# Sensor_Multiplexation.net
KiCad netlist of a schematic drawn in Altium Designer
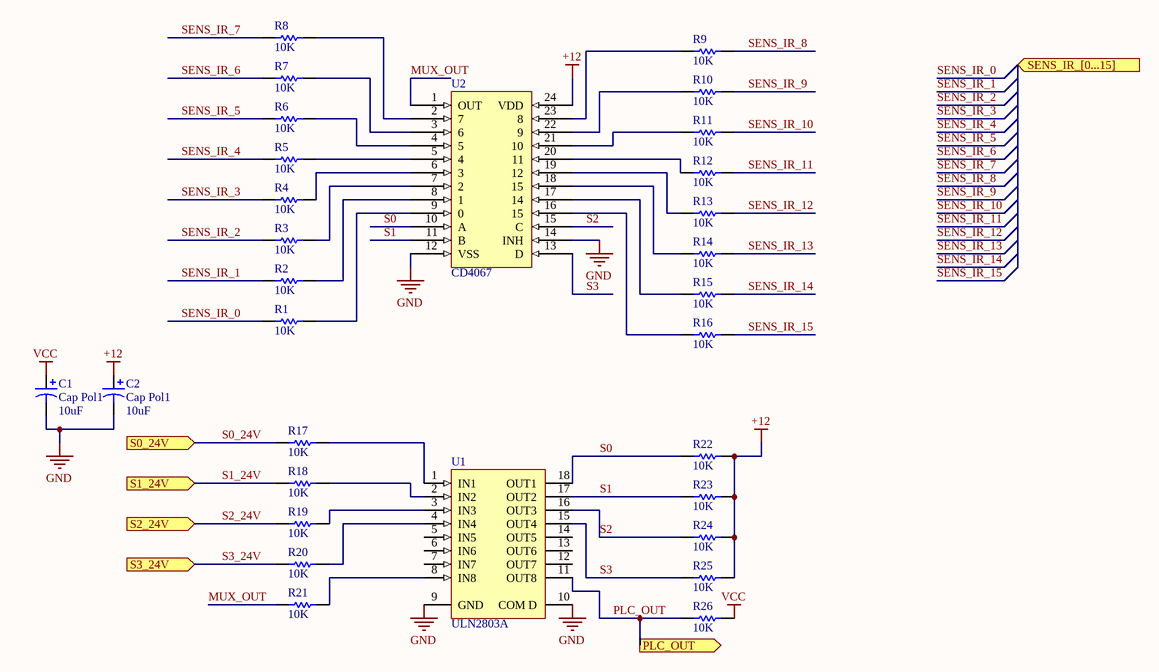
[diagram p0: Sensor_Multiplexation.SchDoc]

(export (version "E")
  (design (tool "Eeschema 10.0.6"))
  (components
    (comp (ref "C1")
      (value "Cap Pol1")
      (footprint "RB7.6-15")
      (description "Polarized Capacitor (Radial)")
      (fields (field (name "ALTIUM_VALUE") "10uF") (field (name "PUBLISHER") "Altium Limited"))
      (libsource (lib "Miscellaneous Devices") (part "Cap Pol1"))
    )
    (comp (ref "C2")
      (value "Cap Pol1")
      (footprint "RB7.6-15")
      (description "Polarized Capacitor (Radial)")
      (fields (field (name "ALTIUM_VALUE") "10uF") (field (name "PUBLISHER") "Altium Limited"))
      (libsource (lib "Miscellaneous Devices") (part "Cap Pol1"))
    )
    (comp (ref "R1")
      (value "10K")
      (footprint "AXIAL-0.3")
      (description "Resistor")
      (fields (field (name "Comment") "Res1") (field (name "PUBLISHER") "Altium Limited"))
      (libsource (lib "Miscellaneous Devices") (part "Res1"))
    )
    (comp (ref "R2")
      (value "10K")
      (footprint "AXIAL-0.3")
      (description "Resistor")
      (fields (field (name "Comment") "Res1") (field (name "PUBLISHER") "Altium Limited"))
      (libsource (lib "Miscellaneous Devices") (part "Res1"))
    )
    (comp (ref "R3")
      (value "10K")
      (footprint "AXIAL-0.3")
      (description "Resistor")
      (fields (field (name "Comment") "Res1") (field (name "PUBLISHER") "Altium Limited"))
      (libsource (lib "Miscellaneous Devices") (part "Res1"))
    )
    (comp (ref "R4")
      (value "10K")
      (footprint "AXIAL-0.3")
      (description "Resistor")
      (fields (field (name "Comment") "Res1") (field (name "PUBLISHER") "Altium Limited"))
      (libsource (lib "Miscellaneous Devices") (part "Res1"))
    )
    (comp (ref "R5")
      (value "10K")
      (footprint "AXIAL-0.3")
      (description "Resistor")
      (fields (field (name "Comment") "Res1") (field (name "PUBLISHER") "Altium Limited"))
      (libsource (lib "Miscellaneous Devices") (part "Res1"))
    )
    (comp (ref "R6")
      (value "10K")
      (footprint "AXIAL-0.3")
      (description "Resistor")
      (fields (field (name "Comment") "Res1") (field (name "PUBLISHER") "Altium Limited"))
      (libsource (lib "Miscellaneous Devices") (part "Res1"))
    )
    (comp (ref "R7")
      (value "10K")
      (footprint "AXIAL-0.3")
      (description "Resistor")
      (fields (field (name "Comment") "Res1") (field (name "PUBLISHER") "Altium Limited"))
      (libsource (lib "Miscellaneous Devices") (part "Res1"))
    )
    (comp (ref "R8")
      (value "10K")
      (footprint "AXIAL-0.3")
      (description "Resistor")
      (fields (field (name "Comment") "Res1") (field (name "PUBLISHER") "Altium Limited"))
      (libsource (lib "Miscellaneous Devices") (part "Res1"))
    )
    (comp (ref "R9")
      (value "10K")
      (footprint "AXIAL-0.3")
      (description "Resistor")
      (fields (field (name "Comment") "Res1") (field (name "PUBLISHER") "Altium Limited"))
      (libsource (lib "Miscellaneous Devices") (part "Res1"))
    )
    (comp (ref "R10")
      (value "10K")
      (footprint "AXIAL-0.3")
      (description "Resistor")
      (fields (field (name "Comment") "Res1") (field (name "PUBLISHER") "Altium Limited"))
      (libsource (lib "Miscellaneous Devices") (part "Res1"))
    )
    (comp (ref "R11")
      (value "10K")
      (footprint "AXIAL-0.3")
      (description "Resistor")
      (fields (field (name "Comment") "Res1") (field (name "PUBLISHER") "Altium Limited"))
      (libsource (lib "Miscellaneous Devices") (part "Res1"))
    )
    (comp (ref "R12")
      (value "10K")
      (footprint "AXIAL-0.3")
      (description "Resistor")
      (fields (field (name "Comment") "Res1") (field (name "PUBLISHER") "Altium Limited"))
      (libsource (lib "Miscellaneous Devices") (part "Res1"))
    )
    (comp (ref "R13")
      (value "10K")
      (footprint "AXIAL-0.3")
      (description "Resistor")
      (fields (field (name "Comment") "Res1") (field (name "PUBLISHER") "Altium Limited"))
      (libsource (lib "Miscellaneous Devices") (part "Res1"))
    )
    (comp (ref "R14")
      (value "10K")
      (footprint "AXIAL-0.3")
      (description "Resistor")
      (fields (field (name "Comment") "Res1") (field (name "PUBLISHER") "Altium Limited"))
      (libsource (lib "Miscellaneous Devices") (part "Res1"))
    )
    (comp (ref "R15")
      (value "10K")
      (footprint "AXIAL-0.3")
      (description "Resistor")
      (fields (field (name "Comment") "Res1") (field (name "PUBLISHER") "Altium Limited"))
      (libsource (lib "Miscellaneous Devices") (part "Res1"))
    )
    (comp (ref "R16")
      (value "10K")
      (footprint "AXIAL-0.3")
      (description "Resistor")
      (fields (field (name "Comment") "Res1") (field (name "PUBLISHER") "Altium Limited"))
      (libsource (lib "Miscellaneous Devices") (part "Res1"))
    )
    (comp (ref "R17")
      (value "10K")
      (footprint "AXIAL-0.3")
      (description "Resistor")
      (fields (field (name "Comment") "Res1") (field (name "PUBLISHER") "Altium Limited"))
      (libsource (lib "Miscellaneous Devices") (part "Res1"))
    )
    (comp (ref "R18")
      (value "10K")
      (footprint "AXIAL-0.3")
      (description "Resistor")
      (fields (field (name "Comment") "Res1") (field (name "PUBLISHER") "Altium Limited"))
      (libsource (lib "Miscellaneous Devices") (part "Res1"))
    )
    (comp (ref "R19")
      (value "10K")
      (footprint "AXIAL-0.3")
      (description "Resistor")
      (fields (field (name "Comment") "Res1") (field (name "PUBLISHER") "Altium Limited"))
      (libsource (lib "Miscellaneous Devices") (part "Res1"))
    )
    (comp (ref "R20")
      (value "10K")
      (footprint "AXIAL-0.3")
      (description "Resistor")
      (fields (field (name "Comment") "Res1") (field (name "PUBLISHER") "Altium Limited"))
      (libsource (lib "Miscellaneous Devices") (part "Res1"))
    )
    (comp (ref "R21")
      (value "10K")
      (footprint "AXIAL-0.3")
      (description "Resistor")
      (fields (field (name "Comment") "Res1") (field (name "PUBLISHER") "Altium Limited"))
      (libsource (lib "Miscellaneous Devices") (part "Res1"))
    )
    (comp (ref "R22")
      (value "10K")
      (footprint "AXIAL-0.3")
      (description "Resistor")
      (fields (field (name "Comment") "Res1") (field (name "PUBLISHER") "Altium Limited"))
      (libsource (lib "Miscellaneous Devices") (part "Res1"))
    )
    (comp (ref "R23")
      (value "10K")
      (footprint "AXIAL-0.3")
      (description "Resistor")
      (fields (field (name "Comment") "Res1") (field (name "PUBLISHER") "Altium Limited"))
      (libsource (lib "Miscellaneous Devices") (part "Res1"))
    )
    (comp (ref "R24")
      (value "10K")
      (footprint "AXIAL-0.3")
      (description "Resistor")
      (fields (field (name "Comment") "Res1") (field (name "PUBLISHER") "Altium Limited"))
      (libsource (lib "Miscellaneous Devices") (part "Res1"))
    )
    (comp (ref "R25")
      (value "10K")
      (footprint "AXIAL-0.3")
      (description "Resistor")
      (fields (field (name "Comment") "Res1") (field (name "PUBLISHER") "Altium Limited"))
      (libsource (lib "Miscellaneous Devices") (part "Res1"))
    )
    (comp (ref "R26")
      (value "10K")
      (footprint "AXIAL-0.3")
      (description "Resistor")
      (fields (field (name "Comment") "Res1") (field (name "PUBLISHER") "Altium Limited"))
      (libsource (lib "Miscellaneous Devices") (part "Res1"))
    )
    (comp (ref "U1")
      (value "ULN2803A")
      (footprint "A18")
      (description "High-Voltage, High-Current Darlington Array")
      (fields (field (name "PUBLISHER") "Altium Limited"))
      (libsource (lib "Allegro Interface Darlington Driver") (part "ULN2803A"))
    )
    (comp (ref "U2") (value "CD4067") (libsource (lib "RobotLib") (part "CD4067")))
  )
  (nets
    (net (code "1") (name "+12") (class "Default")
      (node (ref "C2") (pin "1") (pinfunction "1_1") (pintype "passive"))
      (node (ref "R22") (pin "2") (pinfunction "2_2") (pintype "passive"))
      (node (ref "R23") (pin "2") (pinfunction "2_2") (pintype "passive"))
      (node (ref "R24") (pin "2") (pinfunction "2_2") (pintype "passive"))
      (node (ref "R25") (pin "2") (pinfunction "2_2") (pintype "passive"))
      (node (ref "U2") (pin "24") (pinfunction "VDD_24") (pintype "input"))
    )
    (net (code "2") (name "/MUX_OUT") (class "Default")
      (node (ref "R21") (pin "1") (pinfunction "1_1") (pintype "passive"))
      (node (ref "U2") (pin "1") (pinfunction "OUT_1") (pintype "input"))
    )
    (net (code "3") (name "/PLC_OUT") (class "Default")
      (node (ref "R26") (pin "1") (pinfunction "1_1") (pintype "passive"))
      (node (ref "U1") (pin "11") (pinfunction "OUT8_11") (pintype "open_collector"))
    )
    (net (code "4") (name "/S0") (class "Default")
      (node (ref "R22") (pin "1") (pinfunction "1_1") (pintype "passive"))
      (node (ref "U1") (pin "18") (pinfunction "OUT1_18") (pintype "open_collector"))
      (node (ref "U2") (pin "10") (pinfunction "A_10") (pintype "input"))
    )
    (net (code "5") (name "/S0_24V") (class "Default")
      (node (ref "R17") (pin "1") (pinfunction "1_1") (pintype "passive"))
    )
    (net (code "6") (name "/S1") (class "Default")
      (node (ref "R23") (pin "1") (pinfunction "1_1") (pintype "passive"))
      (node (ref "U1") (pin "17") (pinfunction "OUT2_17") (pintype "open_collector"))
      (node (ref "U2") (pin "11") (pinfunction "B_11") (pintype "input"))
    )
    (net (code "7") (name "/S1_24V") (class "Default")
      (node (ref "R18") (pin "1") (pinfunction "1_1") (pintype "passive"))
    )
    (net (code "8") (name "/S2") (class "Default")
      (node (ref "R24") (pin "1") (pinfunction "1_1") (pintype "passive"))
      (node (ref "U1") (pin "16") (pinfunction "OUT3_16") (pintype "open_collector"))
      (node (ref "U2") (pin "15") (pinfunction "C_15") (pintype "input"))
    )
    (net (code "9") (name "/S2_24V") (class "Default")
      (node (ref "R19") (pin "1") (pinfunction "1_1") (pintype "passive"))
    )
    (net (code "10") (name "/S3") (class "Default")
      (node (ref "R25") (pin "1") (pinfunction "1_1") (pintype "passive"))
      (node (ref "U1") (pin "15") (pinfunction "OUT4_15") (pintype "open_collector"))
      (node (ref "U2") (pin "13") (pinfunction "D_13") (pintype "input"))
    )
    (net (code "11") (name "/S3_24V") (class "Default")
      (node (ref "R20") (pin "1") (pinfunction "1_1") (pintype "passive"))
    )
    (net (code "12") (name "/SENS_IR_0") (class "Default")
      (node (ref "R1") (pin "1") (pinfunction "1_1") (pintype "passive"))
    )
    (net (code "13") (name "/SENS_IR_1") (class "Default")
      (node (ref "R2") (pin "1") (pinfunction "1_1") (pintype "passive"))
    )
    (net (code "14") (name "/SENS_IR_2") (class "Default")
      (node (ref "R3") (pin "1") (pinfunction "1_1") (pintype "passive"))
    )
    (net (code "15") (name "/SENS_IR_3") (class "Default")
      (node (ref "R4") (pin "1") (pinfunction "1_1") (pintype "passive"))
    )
    (net (code "16") (name "/SENS_IR_4") (class "Default")
      (node (ref "R5") (pin "1") (pinfunction "1_1") (pintype "passive"))
    )
    (net (code "17") (name "/SENS_IR_5") (class "Default")
      (node (ref "R6") (pin "1") (pinfunction "1_1") (pintype "passive"))
    )
    (net (code "18") (name "/SENS_IR_6") (class "Default")
      (node (ref "R7") (pin "1") (pinfunction "1_1") (pintype "passive"))
    )
    (net (code "19") (name "/SENS_IR_7") (class "Default")
      (node (ref "R8") (pin "1") (pinfunction "1_1") (pintype "passive"))
    )
    (net (code "20") (name "/SENS_IR_8") (class "Default")
      (node (ref "R9") (pin "2") (pinfunction "2_2") (pintype "passive"))
    )
    (net (code "21") (name "/SENS_IR_9") (class "Default")
      (node (ref "R10") (pin "2") (pinfunction "2_2") (pintype "passive"))
    )
    (net (code "22") (name "/SENS_IR_10") (class "Default")
      (node (ref "R11") (pin "2") (pinfunction "2_2") (pintype "passive"))
    )
    (net (code "23") (name "/SENS_IR_11") (class "Default")
      (node (ref "R12") (pin "2") (pinfunction "2_2") (pintype "passive"))
    )
    (net (code "24") (name "/SENS_IR_12") (class "Default")
      (node (ref "R13") (pin "2") (pinfunction "2_2") (pintype "passive"))
    )
    (net (code "25") (name "/SENS_IR_13") (class "Default")
      (node (ref "R14") (pin "2") (pinfunction "2_2") (pintype "passive"))
    )
    (net (code "26") (name "/SENS_IR_14") (class "Default")
      (node (ref "R15") (pin "2") (pinfunction "2_2") (pintype "passive"))
    )
    (net (code "27") (name "/SENS_IR_15") (class "Default")
      (node (ref "R16") (pin "2") (pinfunction "2_2") (pintype "passive"))
    )
    (net (code "29") (name "GND") (class "Default")
      (node (ref "C1") (pin "2") (pinfunction "2_2") (pintype "passive"))
      (node (ref "C2") (pin "2") (pinfunction "2_2") (pintype "passive"))
      (node (ref "U1") (pin "10") (pinfunction "COM_D_10") (pintype "passive"))
      (node (ref "U1") (pin "9") (pinfunction "GND_9") (pintype "power_in"))
      (node (ref "U2") (pin "12") (pinfunction "VSS_12") (pintype "input"))
      (node (ref "U2") (pin "14") (pinfunction "INH_14") (pintype "input"))
    )
    (net (code "30") (name "Net-(R14-Pad1)") (class "Default")
      (node (ref "R14") (pin "1") (pinfunction "1_1") (pintype "passive"))
      (node (ref "U2") (pin "18") (pinfunction "15_18") (pintype "input"))
    )
    (net (code "31") (name "Net-(R16-Pad1)") (class "Default")
      (node (ref "R16") (pin "1") (pinfunction "1_1") (pintype "passive"))
      (node (ref "U2") (pin "16") (pinfunction "15_16") (pintype "input"))
    )
    (net (code "32") (name "Net-(U1-IN1)") (class "Default")
      (node (ref "R17") (pin "2") (pinfunction "2_2") (pintype "passive"))
      (node (ref "U1") (pin "1") (pinfunction "IN1_1") (pintype "input"))
    )
    (net (code "33") (name "Net-(U1-IN2)") (class "Default")
      (node (ref "R18") (pin "2") (pinfunction "2_2") (pintype "passive"))
      (node (ref "U1") (pin "2") (pinfunction "IN2_2") (pintype "input"))
    )
    (net (code "34") (name "Net-(U1-IN3)") (class "Default")
      (node (ref "R19") (pin "2") (pinfunction "2_2") (pintype "passive"))
      (node (ref "U1") (pin "3") (pinfunction "IN3_3") (pintype "input"))
    )
    (net (code "35") (name "Net-(U1-IN4)") (class "Default")
      (node (ref "R20") (pin "2") (pinfunction "2_2") (pintype "passive"))
      (node (ref "U1") (pin "4") (pinfunction "IN4_4") (pintype "input"))
    )
    (net (code "36") (name "Net-(U1-IN8)") (class "Default")
      (node (ref "R21") (pin "2") (pinfunction "2_2") (pintype "passive"))
      (node (ref "U1") (pin "8") (pinfunction "IN8_8") (pintype "input"))
    )
    (net (code "37") (name "Net-(U2-0)") (class "Default")
      (node (ref "R1") (pin "2") (pinfunction "2_2") (pintype "passive"))
      (node (ref "U2") (pin "9") (pinfunction "0_9") (pintype "input"))
    )
    (net (code "38") (name "Net-(U2-1)") (class "Default")
      (node (ref "R2") (pin "2") (pinfunction "2_2") (pintype "passive"))
      (node (ref "U2") (pin "8") (pinfunction "1_8") (pintype "input"))
    )
    (net (code "39") (name "Net-(U2-2)") (class "Default")
      (node (ref "R3") (pin "2") (pinfunction "2_2") (pintype "passive"))
      (node (ref "U2") (pin "7") (pinfunction "2_7") (pintype "input"))
    )
    (net (code "40") (name "Net-(U2-3)") (class "Default")
      (node (ref "R4") (pin "2") (pinfunction "2_2") (pintype "passive"))
      (node (ref "U2") (pin "6") (pinfunction "3_6") (pintype "input"))
    )
    (net (code "41") (name "Net-(U2-4)") (class "Default")
      (node (ref "R5") (pin "2") (pinfunction "2_2") (pintype "passive"))
      (node (ref "U2") (pin "5") (pinfunction "4_5") (pintype "input"))
    )
    (net (code "42") (name "Net-(U2-5)") (class "Default")
      (node (ref "R6") (pin "2") (pinfunction "2_2") (pintype "passive"))
      (node (ref "U2") (pin "4") (pinfunction "5_4") (pintype "input"))
    )
    (net (code "43") (name "Net-(U2-6)") (class "Default")
      (node (ref "R7") (pin "2") (pinfunction "2_2") (pintype "passive"))
      (node (ref "U2") (pin "3") (pinfunction "6_3") (pintype "input"))
    )
    (net (code "44") (name "Net-(U2-7)") (class "Default")
      (node (ref "R8") (pin "2") (pinfunction "2_2") (pintype "passive"))
      (node (ref "U2") (pin "2") (pinfunction "7_2") (pintype "input"))
    )
    (net (code "45") (name "Net-(U2-8)") (class "Default")
      (node (ref "R9") (pin "1") (pinfunction "1_1") (pintype "passive"))
      (node (ref "U2") (pin "23") (pinfunction "8_23") (pintype "input"))
    )
    (net (code "46") (name "Net-(U2-9)") (class "Default")
      (node (ref "R10") (pin "1") (pinfunction "1_1") (pintype "passive"))
      (node (ref "U2") (pin "22") (pinfunction "9_22") (pintype "input"))
    )
    (net (code "47") (name "Net-(U2-10)") (class "Default")
      (node (ref "R11") (pin "1") (pinfunction "1_1") (pintype "passive"))
      (node (ref "U2") (pin "21") (pinfunction "10_21") (pintype "input"))
    )
    (net (code "48") (name "Net-(U2-11)") (class "Default")
      (node (ref "R12") (pin "1") (pinfunction "1_1") (pintype "passive"))
      (node (ref "U2") (pin "20") (pinfunction "11_20") (pintype "input"))
    )
    (net (code "49") (name "Net-(U2-12)") (class "Default")
      (node (ref "R13") (pin "1") (pinfunction "1_1") (pintype "passive"))
      (node (ref "U2") (pin "19") (pinfunction "12_19") (pintype "input"))
    )
    (net (code "50") (name "Net-(U2-14)") (class "Default")
      (node (ref "R15") (pin "1") (pinfunction "1_1") (pintype "passive"))
      (node (ref "U2") (pin "17") (pinfunction "14_17") (pintype "input"))
    )
    (net (code "51") (name "VCC") (class "Default")
      (node (ref "C1") (pin "1") (pinfunction "1_1") (pintype "passive"))
      (node (ref "R26") (pin "2") (pinfunction "2_2") (pintype "passive"))
    )
    (net (code "52") (name "unconnected-(U1-IN5-Pad5)") (class "Default")
      (node (ref "U1") (pin "5") (pinfunction "IN5_5") (pintype "input"))
    )
    (net (code "53") (name "unconnected-(U1-IN6-Pad6)") (class "Default")
      (node (ref "U1") (pin "6") (pinfunction "IN6_6") (pintype "input"))
    )
    (net (code "54") (name "unconnected-(U1-IN7-Pad7)") (class "Default")
      (node (ref "U1") (pin "7") (pinfunction "IN7_7") (pintype "input"))
    )
    (net (code "55") (name "unconnected-(U1-OUT5-Pad14)") (class "Default")
      (node (ref "U1") (pin "14") (pinfunction "OUT5_14") (pintype "open_collector"))
    )
    (net (code "56") (name "unconnected-(U1-OUT6-Pad13)") (class "Default")
      (node (ref "U1") (pin "13") (pinfunction "OUT6_13") (pintype "open_collector"))
    )
    (net (code "57") (name "unconnected-(U1-OUT7-Pad12)") (class "Default")
      (node (ref "U1") (pin "12") (pinfunction "OUT7_12") (pintype "open_collector"))
    )
  )
)
